# fonte3.net
KiCad netlist of a schematic drawn in EAGLE
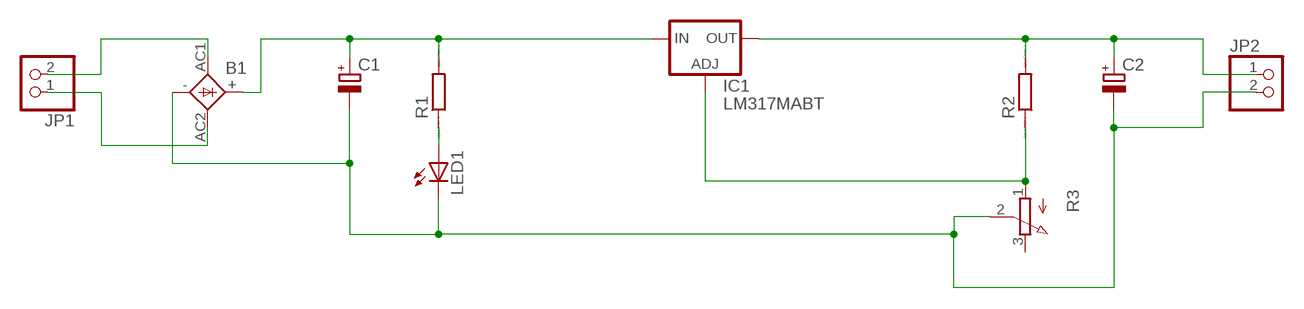
[diagram p0: schematic, sheet 1]

(export (version "E")
  (design (tool "Eeschema 10.0.6"))
  (components
    (comp (ref "B1")
      (value "1KAB")
      (footprint "eagle-import:1KAB")
      (libsource (lib "eagle-import") (part "1KAB"))
    )
    (comp (ref "C1")
      (value "CPOL-EUE5-10.5")
      (footprint "eagle-import:E5-10,5")
      (libsource (lib "eagle-import") (part "CPOL-EUE5-10.5"))
    )
    (comp (ref "C2")
      (value "CPOL-EUE5-10.5")
      (footprint "eagle-import:E5-10,5")
      (libsource (lib "eagle-import") (part "CPOL-EUE5-10.5"))
    )
    (comp (ref "IC1")
      (value "LM317MABT")
      (footprint "eagle-import:TO220L1")
      (libsource (lib "eagle-import") (part "LM317?MABT"))
    )
    (comp (ref "JP1")
      (value "PINHD-1X2")
      (footprint "eagle-import:1X02")
      (libsource (lib "eagle-import") (part "PINHD-1X2"))
    )
    (comp (ref "JP2")
      (value "PINHD-1X2")
      (footprint "eagle-import:1X02")
      (libsource (lib "eagle-import") (part "PINHD-1X2"))
    )
    (comp (ref "LED1")
      (value "LED5MM")
      (footprint "eagle-import:LED5MM")
      (libsource (lib "eagle-import") (part "LED5MM"))
    )
    (comp (ref "R1")
      (value "R0207/10")
      (footprint "eagle-import:0207_10")
      (libsource (lib "eagle-import") (part "R0207/10"))
    )
    (comp (ref "R2")
      (value "R0207/10")
      (footprint "eagle-import:0207_10")
      (libsource (lib "eagle-import") (part "R0207/10"))
    )
    (comp (ref "R3")
      (value "3RP/1610N")
      (footprint "eagle-import:3RP_1610N")
      (libsource (lib "eagle-import") (part "3RP/1610N"))
    )
  )
  (nets
    (net (code "1") (name "Net-(B1-PadAC1)") (class "Default")
      (node (ref "B1") (pin "AC1") (pinfunction "AC1_AC1") (pintype "passive"))
      (node (ref "JP1") (pin "2") (pinfunction "2_2") (pintype "passive"))
    )
    (net (code "2") (name "Net-(B1-PadAC2)") (class "Default")
      (node (ref "B1") (pin "AC2") (pinfunction "AC2_AC2") (pintype "passive"))
      (node (ref "JP1") (pin "1") (pinfunction "1_1") (pintype "passive"))
    )
    (net (code "3") (name "Net-(IC1-ADJ)") (class "Default")
      (node (ref "IC1") (pin "1") (pinfunction "ADJ_1") (pintype "input"))
      (node (ref "R2") (pin "1") (pinfunction "1_1") (pintype "passive"))
      (node (ref "R3") (pin "1") (pinfunction "A_1") (pintype "passive"))
    )
    (net (code "4") (name "Net-(IC1-IN)") (class "Default")
      (node (ref "B1") (pin "+") (pinfunction "+_+") (pintype "passive"))
      (node (ref "C1") (pin "+") (pinfunction "+_+") (pintype "passive"))
      (node (ref "IC1") (pin "3") (pinfunction "IN_3") (pintype "input"))
      (node (ref "R1") (pin "2") (pinfunction "2_2") (pintype "passive"))
    )
    (net (code "5") (name "Net-(IC1-OUT)") (class "Default")
      (node (ref "C2") (pin "+") (pinfunction "+_+") (pintype "passive"))
      (node (ref "IC1") (pin "2") (pinfunction "OUT_2") (pintype "passive"))
      (node (ref "JP2") (pin "1") (pinfunction "1_1") (pintype "passive"))
      (node (ref "R2") (pin "2") (pinfunction "2_2") (pintype "passive"))
    )
    (net (code "6") (name "Net-(LED1-C)") (class "Default")
      (node (ref "B1") (pin "-") (pinfunction "-_-") (pintype "passive"))
      (node (ref "C1") (pin "-") (pinfunction "-_-") (pintype "passive"))
      (node (ref "C2") (pin "-") (pinfunction "-_-") (pintype "passive"))
      (node (ref "JP2") (pin "2") (pinfunction "2_2") (pintype "passive"))
      (node (ref "LED1") (pin "K") (pinfunction "C_K") (pintype "passive"))
      (node (ref "R3") (pin "2") (pinfunction "S_2") (pintype "passive"))
    )
    (net (code "7") (name "Net-(LED1-PadA)") (class "Default")
      (node (ref "LED1") (pin "A") (pinfunction "A_A") (pintype "passive"))
      (node (ref "R1") (pin "1") (pinfunction "1_1") (pintype "passive"))
    )
    (net (code "8") (name "unconnected-(R3-E-Pad3)") (class "Default")
      (node (ref "R3") (pin "3") (pinfunction "E_3") (pintype "passive"))
    )
  )
)
